# Power_supply.net
KiCad netlist of a schematic drawn in Altium Designer
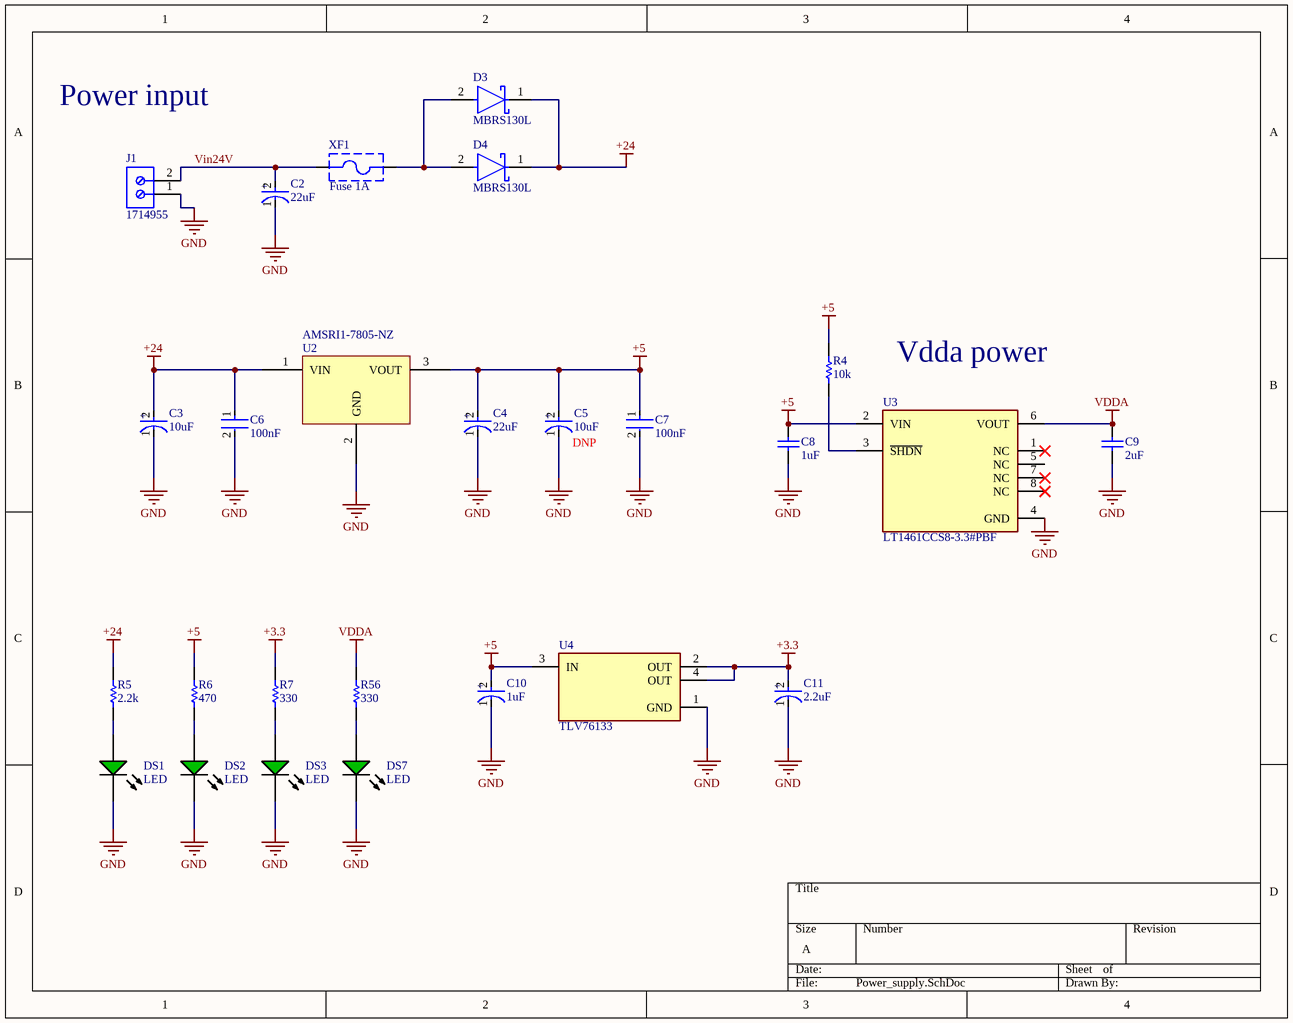
[diagram p0: Power_supply.SchDoc]

(export (version "E")
  (design (tool "Eeschema 10.0.6"))
  (components
    (comp (ref "C2")
      (value "22uF")
      (footprint "FP-FCE-MFG")
      (description "CAP ALUM 22UF 20% 50V SMD")
      (fields (field (name "VOLTAGE") "50V") (field (name "TOLERANCE") "20%"))
      (libsource (lib "Altium Content Vault") (part "a00bbbee19879c290e62620ae7e47b1"))
    )
    (comp (ref "C3")
      (value "10uF")
      (footprint "FP-FKD-MFG")
      (description "CAP ALUM 10UF 20% 50V SMD")
      (fields (field (name "VOLTAGE") "50V") (field (name "TOLERANCE") "20%"))
      (libsource (lib "Altium Content Vault") (part "203bc49f2ac43e59fd269a8c329ed05"))
    )
    (comp (ref "C4")
      (value "22uF")
      (footprint "FP-FCE-MFG")
      (description "CAP ALUM 22UF 20% 50V SMD")
      (fields (field (name "VOLTAGE") "50V") (field (name "TOLERANCE") "20%"))
      (libsource (lib "Altium Content Vault") (part "a00bbbee19879c290e62620ae7e47b1"))
    )
    (comp (ref "C5")
      (value "10uF")
      (footprint "FP-FKD-MFG")
      (description "CAP ALUM 10UF 20% 50V SMD")
      (fields (field (name "VOLTAGE") "50V") (field (name "TOLERANCE") "20%"))
      (libsource (lib "Altium Content Vault") (part "203bc49f2ac43e59fd269a8c329ed05"))
    )
    (comp (ref "C6")
      (value "100nF")
      (footprint "FP-0805-L_2_01_0_2-W_1_25-IPC_B")
      (description "General Purpose Ceramic Capacitor, 0805, 10nF, 10%, X7R, 15%, 100V")
      (fields (field (name "VOLTAGE") "100V") (field (name "TOLERANCE") "10%"))
      (libsource (lib "Altium Content Vault") (part "b4654b650e69147ec39a6b967a45e02"))
    )
    (comp (ref "C7")
      (value "100nF")
      (footprint "FP-0805-L_2_01_0_2-W_1_25-IPC_B")
      (description "General Purpose Ceramic Capacitor, 0805, 10nF, 10%, X7R, 15%, 100V")
      (fields (field (name "VOLTAGE") "100V") (field (name "TOLERANCE") "10%"))
      (libsource (lib "Altium Content Vault") (part "b4654b650e69147ec39a6b967a45e02"))
    )
    (comp (ref "C8")
      (value "1uF")
      (footprint "CAPC2013X140X50LL20T25")
      (fields (field (name "PART NUMBER") "C0805C105K3RACTU") (field (name "MANUFACTURER") "Kemet"))
      (libsource (lib "Altium Content Vault") (part "CAP"))
    )
    (comp (ref "C9")
      (value "2uF")
      (footprint "CAPC2013X140X50LL20T25")
      (fields (field (name "PART NUMBER") "C0805C105K3RACTU") (field (name "MANUFACTURER") "Kemet"))
      (libsource (lib "Altium Content Vault") (part "CAP"))
    )
    (comp (ref "C10")
      (value "1uF")
      (footprint "FP-FKD-MFG")
      (description "CAP ALUM 10UF 20% 50V SMD")
      (fields (field (name "VOLTAGE") "50V") (field (name "TOLERANCE") "20%"))
      (libsource (lib "Altium Content Vault") (part "203bc49f2ac43e59fd269a8c329ed05"))
    )
    (comp (ref "C11")
      (value "2.2uF")
      (footprint "FP-FKD-MFG")
      (description "CAP ALUM 10UF 20% 50V SMD")
      (fields (field (name "VOLTAGE") "50V") (field (name "TOLERANCE") "20%"))
      (libsource (lib "Altium Content Vault") (part "203bc49f2ac43e59fd269a8c329ed05"))
    )
    (comp (ref "D3")
      (value "MBRS130L")
      (footprint "FP-403AF-MFG")
      (description "MBRS130L Rectifier Diode, Schottky, 1 Phase, 1 Element, 2A, 30V V(RRM), Silicon, DO-214AA")
      (libsource (lib "Altium Content Vault") (part "1d6ec82d83fb6aee721767c19dac4b9"))
    )
    (comp (ref "D4")
      (value "MBRS130L")
      (footprint "FP-403AF-MFG")
      (description "MBRS130L Rectifier Diode, Schottky, 1 Phase, 1 Element, 2A, 30V V(RRM), Silicon, DO-214AA")
      (libsource (lib "Altium Content Vault") (part "1d6ec82d83fb6aee721767c19dac4b9"))
    )
    (comp (ref "DS1")
      (value "LED")
      (footprint "AVAG-HSMX-C170_V")
      (description "Chip LED, Green, 2.2 V, -40 to 85 degC, 2-Pin SMD, Pb-Free, Tape and Reel")
      (fields (field (name "MANUFACTURER") "Avago"))
      (libsource (lib "Altium Content Vault") (part "LED_GREEN_A1K2-2"))
    )
    (comp (ref "DS2")
      (value "LED")
      (footprint "AVAG-HSMX-C170_V")
      (description "Chip LED, Green, 2.2 V, -40 to 85 degC, 2-Pin SMD, Pb-Free, Tape and Reel")
      (fields (field (name "MANUFACTURER") "Avago"))
      (libsource (lib "Altium Content Vault") (part "LED_GREEN_A1K2-2"))
    )
    (comp (ref "DS3")
      (value "LED")
      (footprint "AVAG-HSMX-C170_V")
      (description "Chip LED, Green, 2.2 V, -40 to 85 degC, 2-Pin SMD, Pb-Free, Tape and Reel")
      (fields (field (name "MANUFACTURER") "Avago"))
      (libsource (lib "Altium Content Vault") (part "LED_GREEN_A1K2-2"))
    )
    (comp (ref "DS7")
      (value "LED")
      (footprint "AVAG-HSMX-C170_V")
      (description "Chip LED, Green, 2.2 V, -40 to 85 degC, 2-Pin SMD, Pb-Free, Tape and Reel")
      (fields (field (name "MANUFACTURER") "Avago"))
      (libsource (lib "Altium Content Vault") (part "LED_GREEN_A1K2-2"))
    )
    (comp (ref "J1")
      (value "1714955")
      (footprint "PHOE-1714955_V")
      (description "PC Terminal Block, Pitch 6.35 mm, 1 x 2 Position, Height 21.5 mm, Tail Lenght 5.1 mm, RoHS, Bulk")
      (fields (field (name "MANUFACTURER") "Phoenix Contact"))
      (libsource (lib "Altium Content Vault") (part "CN-1P-F-TB2"))
    )
    (comp (ref "R4")
      (value "10k")
      (footprint "RESC2013X50X30LL20T20")
      (fields (field (name "MANUFACTURER") "Vishay Dale") (field (name "PART NUMBER") "CRCW08050000Z0EA"))
      (libsource (lib "Altium Content Vault") (part "RES"))
    )
    (comp (ref "R5")
      (value "2.2k")
      (footprint "RESC2013X50X30LL20T20")
      (fields (field (name "MANUFACTURER") "Vishay Dale") (field (name "PART NUMBER") "CRCW08050000Z0EA"))
      (libsource (lib "Altium Content Vault") (part "RES"))
    )
    (comp (ref "R6")
      (value "470")
      (footprint "RESC2013X50X30LL20T20")
      (fields (field (name "MANUFACTURER") "Vishay Dale") (field (name "PART NUMBER") "CRCW08050000Z0EA"))
      (libsource (lib "Altium Content Vault") (part "RES"))
    )
    (comp (ref "R7")
      (value "330")
      (footprint "RESC2013X50X30LL20T20")
      (fields (field (name "MANUFACTURER") "Vishay Dale") (field (name "PART NUMBER") "CRCW08050000Z0EA"))
      (libsource (lib "Altium Content Vault") (part "RES"))
    )
    (comp (ref "R56")
      (value "330")
      (footprint "RESC2013X50X30LL20T20")
      (fields (field (name "MANUFACTURER") "Vishay Dale") (field (name "PART NUMBER") "CRCW08050000Z0EA"))
      (libsource (lib "Altium Content Vault") (part "RES"))
    )
    (comp (ref "U2")
      (value "AMSRI1-7805-NZ")
      (footprint "SIP750W46P254L1400H1010Q3")
      (description "AMSRI1-7805-NZ, 5V / 1A DC output converter")
      (libsource (lib "Schematic_library") (part "AMSRI1-7805-NZ"))
    )
    (comp (ref "U3")
      (value "LT1461CCS8-3.3#PBF")
      (footprint "FP-S8-8-05-08-1610-IPC_A")
      (description "IC VREF SERIES 0.08% 8SOIC")
      (fields (field (name "TOLERANCE") "0.08%"))
      (libsource (lib "Altium Content Vault") (part "89c9ffe9d60ac6c934f8caf59899f03"))
    )
    (comp (ref "U4")
      (value "TLV76133")
      (footprint "FP-DCY0004A-MFG")
      (description "TLV76133 1-A 16-V high-PSRR linear voltage regulator 4-SOT-223 -40 to 125")
      (libsource (lib "Altium Content Vault") (part "991ffb903c51cf6179ce9942c0606aa"))
    )
    (comp (ref "XF1")
      (value "Fuse 1A")
      (footprint "696106003002")
      (libsource (lib "Altium Content Vault") (part "Fuse Holder"))
    )
  )
  (nets
    (net (code "1") (name "+3.3") (class "Default")
      (node (ref "C11") (pin "2") (pinfunction "A_2") (pintype "passive"))
      (node (ref "R7") (pin "2") (pinfunction "2_2") (pintype "passive"))
      (node (ref "U4") (pin "2") (pinfunction "OUT_2") (pintype "passive"))
      (node (ref "U4") (pin "4") (pinfunction "OUT_4") (pintype "passive"))
    )
    (net (code "2") (name "+5") (class "Default")
      (node (ref "C10") (pin "2") (pinfunction "A_2") (pintype "passive"))
      (node (ref "C4") (pin "2") (pinfunction "A_2") (pintype "passive"))
      (node (ref "C5") (pin "2") (pinfunction "A_2") (pintype "passive"))
      (node (ref "C7") (pin "1") (pinfunction "1_1") (pintype "passive"))
      (node (ref "C8") (pin "2") (pinfunction "2_2") (pintype "passive"))
      (node (ref "R4") (pin "2") (pinfunction "2_2") (pintype "passive"))
      (node (ref "R6") (pin "2") (pinfunction "2_2") (pintype "passive"))
      (node (ref "U2") (pin "3") (pinfunction "VOUT_3") (pintype "passive"))
      (node (ref "U3") (pin "2") (pinfunction "VIN_2") (pintype "power_in"))
      (node (ref "U4") (pin "3") (pinfunction "IN_3") (pintype "power_in"))
    )
    (net (code "3") (name "+24") (class "Default")
      (node (ref "C3") (pin "2") (pinfunction "A_2") (pintype "passive"))
      (node (ref "C6") (pin "1") (pinfunction "1_1") (pintype "passive"))
      (node (ref "D3") (pin "1") (pinfunction "C_1") (pintype "passive"))
      (node (ref "D4") (pin "1") (pinfunction "C_1") (pintype "passive"))
      (node (ref "R5") (pin "2") (pinfunction "2_2") (pintype "passive"))
      (node (ref "U2") (pin "1") (pinfunction "VIN_1") (pintype "passive"))
    )
    (net (code "4") (name "/Vin24V") (class "Default")
      (node (ref "C2") (pin "2") (pinfunction "A_2") (pintype "passive"))
      (node (ref "J1") (pin "2") (pinfunction "2_2") (pintype "passive"))
      (node (ref "XF1") (pin "1") (pinfunction "1_1") (pintype "passive"))
    )
    (net (code "5") (name "GND") (class "Default")
      (node (ref "C10") (pin "1") (pinfunction "C_1") (pintype "passive"))
      (node (ref "C11") (pin "1") (pinfunction "C_1") (pintype "passive"))
      (node (ref "C2") (pin "1") (pinfunction "C_1") (pintype "passive"))
      (node (ref "C3") (pin "1") (pinfunction "C_1") (pintype "passive"))
      (node (ref "C4") (pin "1") (pinfunction "C_1") (pintype "passive"))
      (node (ref "C5") (pin "1") (pinfunction "C_1") (pintype "passive"))
      (node (ref "C6") (pin "2") (pinfunction "2_2") (pintype "passive"))
      (node (ref "C7") (pin "2") (pinfunction "2_2") (pintype "passive"))
      (node (ref "C8") (pin "1") (pinfunction "1_1") (pintype "passive"))
      (node (ref "C9") (pin "1") (pinfunction "1_1") (pintype "passive"))
      (node (ref "DS1") (pin "2") (pinfunction "K_2") (pintype "passive"))
      (node (ref "DS2") (pin "2") (pinfunction "K_2") (pintype "passive"))
      (node (ref "DS3") (pin "2") (pinfunction "K_2") (pintype "passive"))
      (node (ref "DS7") (pin "2") (pinfunction "K_2") (pintype "passive"))
      (node (ref "J1") (pin "1") (pinfunction "1_1") (pintype "passive"))
      (node (ref "U2") (pin "2") (pinfunction "GND_2") (pintype "passive"))
      (node (ref "U3") (pin "4") (pinfunction "GND_4") (pintype "power_in"))
      (node (ref "U4") (pin "1") (pinfunction "GND_1") (pintype "power_in"))
    )
    (net (code "6") (name "Net-(D3-A)") (class "Default")
      (node (ref "D3") (pin "2") (pinfunction "A_2") (pintype "passive"))
      (node (ref "D4") (pin "2") (pinfunction "A_2") (pintype "passive"))
      (node (ref "XF1") (pin "2") (pinfunction "2_2") (pintype "passive"))
    )
    (net (code "7") (name "Net-(DS1-A)") (class "Default")
      (node (ref "DS1") (pin "1") (pinfunction "A_1") (pintype "passive"))
      (node (ref "R5") (pin "1") (pinfunction "1_1") (pintype "passive"))
    )
    (net (code "8") (name "Net-(DS2-A)") (class "Default")
      (node (ref "DS2") (pin "1") (pinfunction "A_1") (pintype "passive"))
      (node (ref "R6") (pin "1") (pinfunction "1_1") (pintype "passive"))
    )
    (net (code "9") (name "Net-(DS3-A)") (class "Default")
      (node (ref "DS3") (pin "1") (pinfunction "A_1") (pintype "passive"))
      (node (ref "R7") (pin "1") (pinfunction "1_1") (pintype "passive"))
    )
    (net (code "10") (name "Net-(DS7-A)") (class "Default")
      (node (ref "DS7") (pin "1") (pinfunction "A_1") (pintype "passive"))
      (node (ref "R56") (pin "1") (pinfunction "1_1") (pintype "passive"))
    )
    (net (code "11") (name "Net-(U3-~{SHDN})") (class "Default")
      (node (ref "R4") (pin "1") (pinfunction "1_1") (pintype "passive"))
      (node (ref "U3") (pin "3") (pinfunction "~{SHDN}_3") (pintype "passive"))
    )
    (net (code "12") (name "VDDA") (class "Default")
      (node (ref "C9") (pin "2") (pinfunction "2_2") (pintype "passive"))
      (node (ref "R56") (pin "2") (pinfunction "2_2") (pintype "passive"))
      (node (ref "U3") (pin "6") (pinfunction "VOUT_6") (pintype "power_in"))
    )
    (net (code "13") (name "unconnected-(U3-NC-Pad1)") (class "Default")
      (node (ref "U3") (pin "1") (pinfunction "NC_1") (pintype "passive+no_connect"))
    )
    (net (code "14") (name "unconnected-(U3-NC-Pad5)") (class "Default")
      (node (ref "U3") (pin "5") (pinfunction "NC_5") (pintype "passive"))
    )
    (net (code "15") (name "unconnected-(U3-NC-Pad7)") (class "Default")
      (node (ref "U3") (pin "7") (pinfunction "NC_7") (pintype "passive+no_connect"))
    )
    (net (code "16") (name "unconnected-(U3-NC-Pad8)") (class "Default")
      (node (ref "U3") (pin "8") (pinfunction "NC_8") (pintype "passive+no_connect"))
    )
  )
)
